# lra.net
KiCad netlist of a schematic drawn in EAGLE
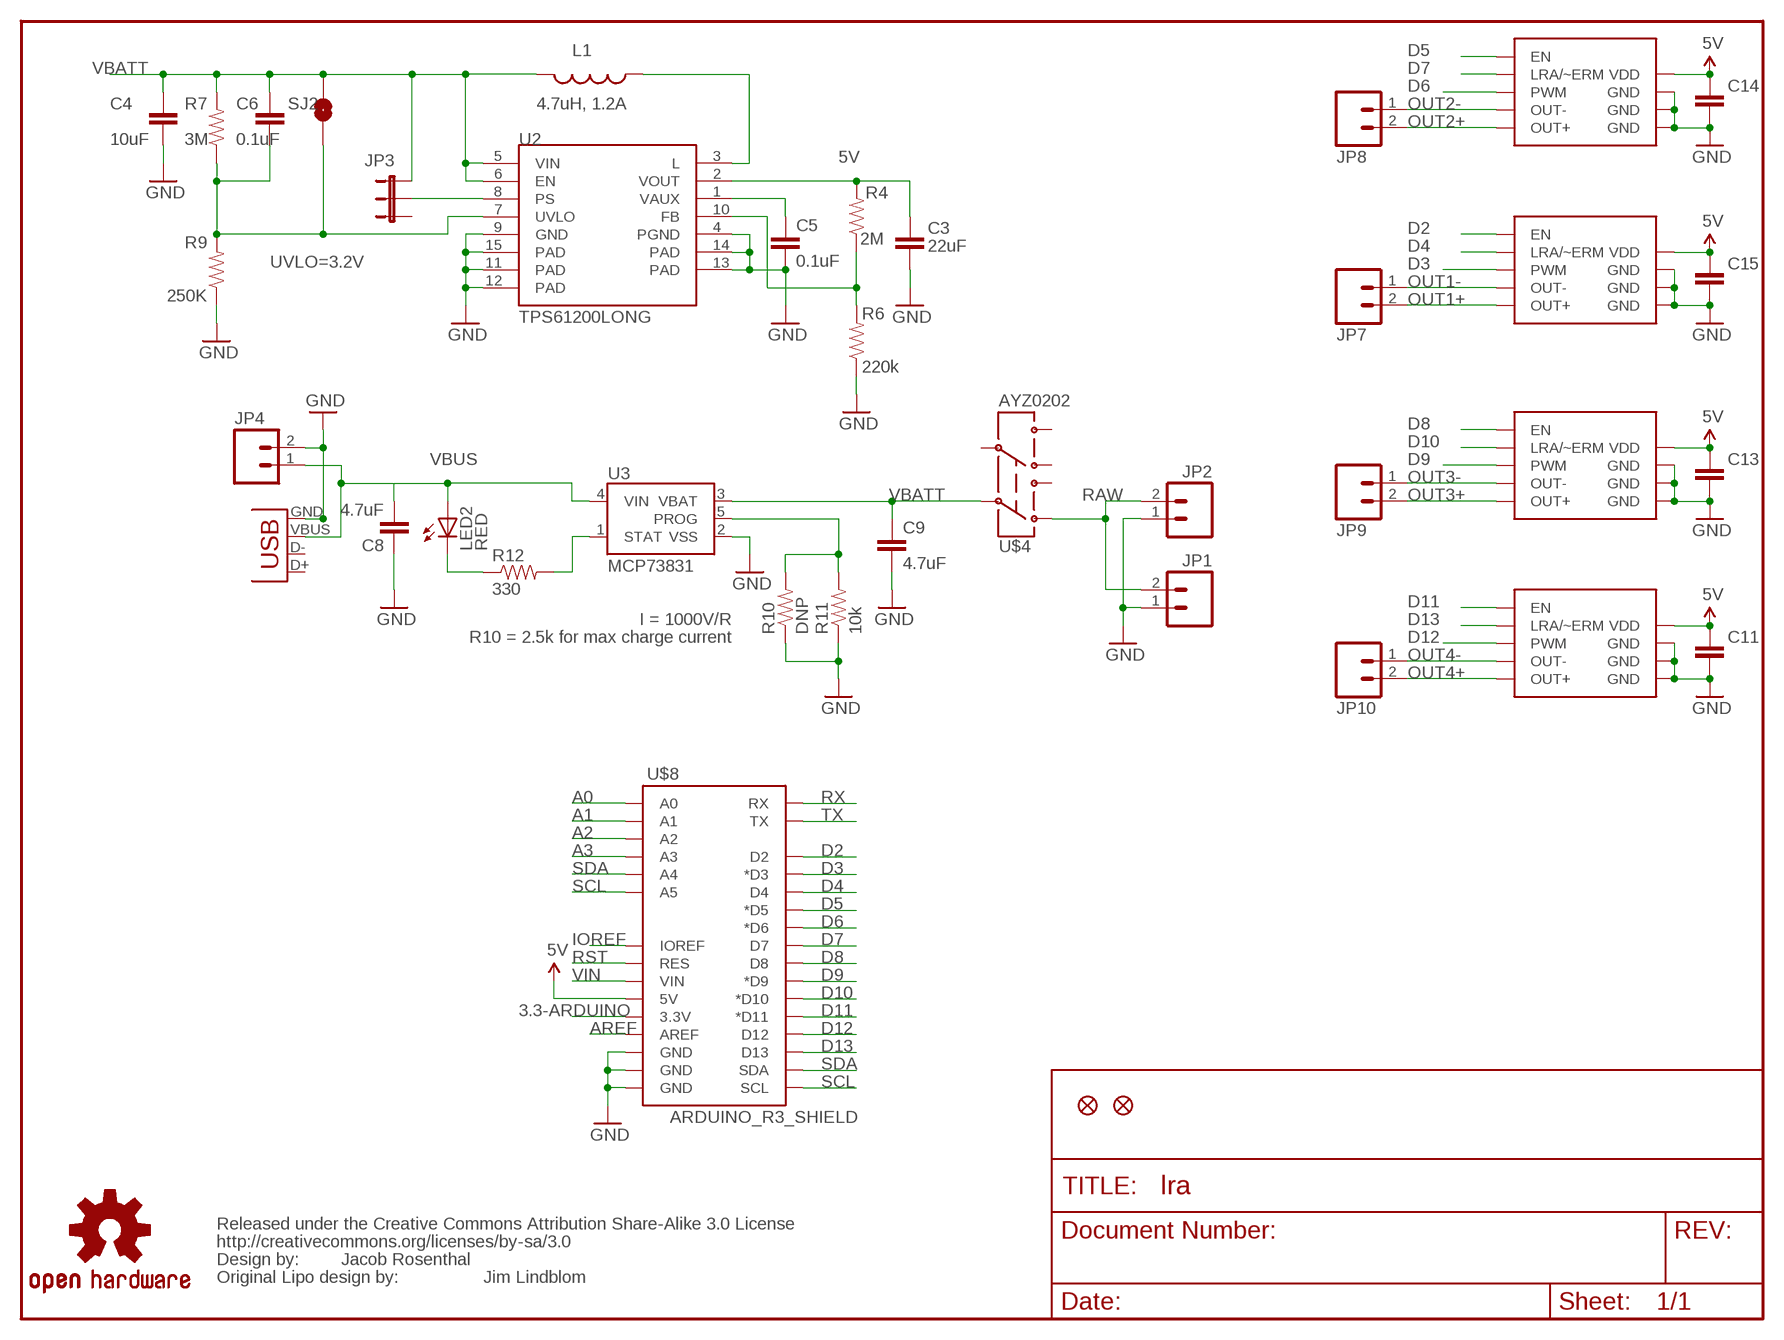
[diagram p0: schematic, sheet 1]

(export (version "E")
  (design (tool "Eeschema 10.0.6"))
  (components
    (comp (ref "$$U$1")
      (value "CREATIVE_COMMONS")
      (footprint "eagle-import:CREATIVE_COMMONS")
      (libsource (lib "eagle-import") (part "CREATIVE_COMMONS"))
    )
    (comp (ref "C3")
      (value "22uF")
      (footprint "eagle-import:0805")
      (libsource (lib "eagle-import") (part "SparkFun_CAP0805"))
    )
    (comp (ref "C4")
      (value "10uF")
      (footprint "eagle-import:0805")
      (libsource (lib "eagle-import") (part "SparkFun_CAP0805"))
    )
    (comp (ref "C5")
      (value "0.1uF")
      (footprint "eagle-import:0805")
      (libsource (lib "eagle-import") (part "SparkFun_CAP0805"))
    )
    (comp (ref "C6")
      (value "0.1uF")
      (footprint "eagle-import:0805")
      (libsource (lib "eagle-import") (part "SparkFun_CAP0805"))
    )
    (comp (ref "C8")
      (value "4.7uF")
      (footprint "eagle-import:0805")
      (libsource (lib "eagle-import") (part "SparkFun_CAP0805"))
    )
    (comp (ref "C9")
      (value "4.7uF")
      (footprint "eagle-import:0805")
      (libsource (lib "eagle-import") (part "SparkFun_CAP0805"))
    )
    (comp (ref "C11")
      (value "CAP0805")
      (footprint "eagle-import:0805")
      (libsource (lib "eagle-import") (part "CAP0805"))
    )
    (comp (ref "C13")
      (value "CAP0805")
      (footprint "eagle-import:0805")
      (libsource (lib "eagle-import") (part "CAP0805"))
    )
    (comp (ref "C14")
      (value "CAP0805")
      (footprint "eagle-import:0805")
      (libsource (lib "eagle-import") (part "CAP0805"))
    )
    (comp (ref "C15")
      (value "CAP0805")
      (footprint "eagle-import:0805")
      (libsource (lib "eagle-import") (part "CAP0805"))
    )
    (comp (ref "JP1")
      (value "M021X02_NO_SILK")
      (footprint "eagle-import:1X02_NO_SILK")
      (libsource (lib "eagle-import") (part "M021X02_NO_SILK"))
    )
    (comp (ref "JP2")
      (value "M02-JST-2MM-SMT")
      (footprint "eagle-import:JST-2-SMD")
      (libsource (lib "eagle-import") (part "M02-JST-2MM-SMT"))
    )
    (comp (ref "JP3")
      (value "JUMPER-32-3")
      (footprint "eagle-import:SJ_3_PASTE2&3")
      (libsource (lib "eagle-import") (part "JUMPER-32-3"))
    )
    (comp (ref "JP4")
      (value "M021X02_NO_SILK")
      (footprint "eagle-import:1X02_NO_SILK")
      (libsource (lib "eagle-import") (part "M021X02_NO_SILK"))
    )
    (comp (ref "JP5")
      (value "FIDUCIAL1X2.5")
      (footprint "eagle-import:FIDUCIAL-1X2.5")
      (libsource (lib "eagle-import") (part "FIDUCIAL1X2.5"))
    )
    (comp (ref "JP6")
      (value "FIDUCIAL1X2.5")
      (footprint "eagle-import:FIDUCIAL-1X2.5")
      (libsource (lib "eagle-import") (part "FIDUCIAL1X2.5"))
    )
    (comp (ref "JP7")
      (value "M02PTH3")
      (footprint "eagle-import:1X02_LONGPADS")
      (libsource (lib "eagle-import") (part "M02PTH3"))
    )
    (comp (ref "JP8")
      (value "M02PTH3")
      (footprint "eagle-import:1X02_LONGPADS")
      (libsource (lib "eagle-import") (part "M02PTH3"))
    )
    (comp (ref "JP9")
      (value "M02PTH3")
      (footprint "eagle-import:1X02_LONGPADS")
      (libsource (lib "eagle-import") (part "M02PTH3"))
    )
    (comp (ref "JP10")
      (value "M02PTH3")
      (footprint "eagle-import:1X02_LONGPADS")
      (libsource (lib "eagle-import") (part "M02PTH3"))
    )
    (comp (ref "L1")
      (value "4.7uH, 1.2A")
      (footprint "eagle-import:CDRH2D09")
      (libsource (lib "eagle-import") (part "INDUCTOR."))
    )
    (comp (ref "LED2")
      (value "RED")
      (footprint "eagle-import:CHIP-LED0805")
      (libsource (lib "eagle-import") (part "LEDCHIP-LED0805"))
    )
    (comp (ref "R4")
      (value "2M")
      (footprint "eagle-import:0805")
      (libsource (lib "eagle-import") (part "RESISTOR0805-RES"))
    )
    (comp (ref "R6")
      (value "220k")
      (footprint "eagle-import:0805")
      (libsource (lib "eagle-import") (part "RESISTOR0805-RES"))
    )
    (comp (ref "R7")
      (value "3M")
      (footprint "eagle-import:0805")
      (libsource (lib "eagle-import") (part "RESISTOR0805-RES"))
    )
    (comp (ref "R9")
      (value "250K")
      (footprint "eagle-import:0805")
      (libsource (lib "eagle-import") (part "RESISTOR0805-RES"))
    )
    (comp (ref "R10")
      (value "DNP")
      (footprint "eagle-import:0805")
      (libsource (lib "eagle-import") (part "RESISTOR0805-RES"))
    )
    (comp (ref "R11")
      (value "10k")
      (footprint "eagle-import:0805")
      (libsource (lib "eagle-import") (part "RESISTOR0805-RES"))
    )
    (comp (ref "R12")
      (value "330")
      (footprint "eagle-import:0805")
      (libsource (lib "eagle-import") (part "RESISTOR0805-RES"))
    )
    (comp (ref "SJ2")
      (value "Power Saving Off")
      (footprint "eagle-import:SJ_2S-NO")
      (libsource (lib "eagle-import") (part "SOLDERJUMPERNO"))
    )
    (comp (ref "U$2")
      (value "DRV260310WFQFN")
      (footprint "eagle-import:10WFQFN")
      (libsource (lib "eagle-import") (part "DRV260310WFQFN"))
    )
    (comp (ref "U$3")
      (value "DRV260310WFQFN")
      (footprint "eagle-import:10WFQFN")
      (libsource (lib "eagle-import") (part "DRV260310WFQFN"))
    )
    (comp (ref "U$4")
      (value "AYZ0202")
      (footprint "eagle-import:AYZ0202")
      (libsource (lib "eagle-import") (part "AYZ0202"))
    )
    (comp (ref "U$6")
      (value "DRV260310WFQFN")
      (footprint "eagle-import:10WFQFN")
      (libsource (lib "eagle-import") (part "DRV260310WFQFN"))
    )
    (comp (ref "U$7")
      (value "DRV2603")
      (footprint "eagle-import:10WFQFN-LONG")
      (libsource (lib "eagle-import") (part "DRV2603"))
    )
    (comp (ref "U$8")
      (value "ARDUINO_R3_SHIELD")
      (footprint "eagle-import:UNO_R3_SHIELD")
      (libsource (lib "eagle-import") (part "ARDUINO_R3_SHIELD"))
    )
    (comp (ref "U$100")
      (value "OSHW-LOGOM")
      (footprint "eagle-import:OSHW-LOGO-M")
      (libsource (lib "eagle-import") (part "OSHW-LOGOM"))
    )
    (comp (ref "U2")
      (value "TPS61200LONG")
      (footprint "eagle-import:QFN-10_PAD_LONG")
      (libsource (lib "eagle-import") (part "TPS61200LONG"))
    )
    (comp (ref "U3")
      (value "MCP73831")
      (footprint "eagle-import:SOT23-5")
      (libsource (lib "eagle-import") (part "MCP73831"))
    )
    (comp (ref "X1")
      (value "USBSMD")
      (footprint "eagle-import:USB-MINIB")
      (libsource (lib "eagle-import") (part "USBSMD"))
    )
  )
  (nets
    (net (code "1") (name "/3.3-ARDUINO") (class "Default")
      (node (ref "U$8") (pin "3.3V") (pinfunction "3.3V_3.3V") (pintype "bidirectional"))
    )
    (net (code "2") (name "/A0") (class "Default")
      (node (ref "U$8") (pin "A0") (pinfunction "A0_A0") (pintype "bidirectional"))
    )
    (net (code "3") (name "/A1") (class "Default")
      (node (ref "U$8") (pin "A1") (pinfunction "A1_A1") (pintype "bidirectional"))
    )
    (net (code "4") (name "/A2") (class "Default")
      (node (ref "U$8") (pin "A2") (pinfunction "A2_A2") (pintype "bidirectional"))
    )
    (net (code "5") (name "/A3") (class "Default")
      (node (ref "U$8") (pin "A3") (pinfunction "A3_A3") (pintype "bidirectional"))
    )
    (net (code "6") (name "/AREF") (class "Default")
      (node (ref "U$8") (pin "AREF") (pinfunction "AREF_AREF") (pintype "bidirectional"))
    )
    (net (code "7") (name "/D2") (class "Default")
      (node (ref "U$3") (pin "P$1") (pinfunction "EN_P$1") (pintype "bidirectional"))
      (node (ref "U$8") (pin "D2") (pinfunction "D2_D2") (pintype "bidirectional"))
    )
    (net (code "8") (name "/D3") (class "Default")
      (node (ref "U$3") (pin "P$2") (pinfunction "PWM_P$2") (pintype "bidirectional"))
      (node (ref "U$8") (pin "D3") (pinfunction "*D3_D3") (pintype "bidirectional"))
    )
    (net (code "9") (name "/D4") (class "Default")
      (node (ref "U$3") (pin "P$3") (pinfunction "LRA/~{ERM}_P$3") (pintype "bidirectional"))
      (node (ref "U$8") (pin "D4") (pinfunction "D4_D4") (pintype "bidirectional"))
    )
    (net (code "10") (name "/D5") (class "Default")
      (node (ref "U$2") (pin "P$1") (pinfunction "EN_P$1") (pintype "bidirectional"))
      (node (ref "U$8") (pin "D5") (pinfunction "*D5_D5") (pintype "bidirectional"))
    )
    (net (code "11") (name "/D6") (class "Default")
      (node (ref "U$2") (pin "P$2") (pinfunction "PWM_P$2") (pintype "bidirectional"))
      (node (ref "U$8") (pin "D6") (pinfunction "*D6_D6") (pintype "bidirectional"))
    )
    (net (code "12") (name "/D7") (class "Default")
      (node (ref "U$2") (pin "P$3") (pinfunction "LRA/~{ERM}_P$3") (pintype "bidirectional"))
      (node (ref "U$8") (pin "D7") (pinfunction "D7_D7") (pintype "bidirectional"))
    )
    (net (code "13") (name "/D8") (class "Default")
      (node (ref "U$6") (pin "P$1") (pinfunction "EN_P$1") (pintype "bidirectional"))
      (node (ref "U$8") (pin "D8") (pinfunction "D8_D8") (pintype "bidirectional"))
    )
    (net (code "14") (name "/D9") (class "Default")
      (node (ref "U$6") (pin "P$2") (pinfunction "PWM_P$2") (pintype "bidirectional"))
      (node (ref "U$8") (pin "D9") (pinfunction "*D9_D9") (pintype "bidirectional"))
    )
    (net (code "15") (name "/D10") (class "Default")
      (node (ref "U$6") (pin "P$3") (pinfunction "LRA/~{ERM}_P$3") (pintype "bidirectional"))
      (node (ref "U$8") (pin "D10") (pinfunction "*D10_D10") (pintype "bidirectional"))
    )
    (net (code "16") (name "/D11") (class "Default")
      (node (ref "U$7") (pin "P$1") (pinfunction "EN_P$1") (pintype "bidirectional"))
      (node (ref "U$8") (pin "D11") (pinfunction "*D11_D11") (pintype "bidirectional"))
    )
    (net (code "17") (name "/D12") (class "Default")
      (node (ref "U$7") (pin "P$2") (pinfunction "PWM_P$2") (pintype "bidirectional"))
      (node (ref "U$8") (pin "D12") (pinfunction "D12_D12") (pintype "bidirectional"))
    )
    (net (code "18") (name "/D13") (class "Default")
      (node (ref "U$7") (pin "P$3") (pinfunction "LRA/~{ERM}_P$3") (pintype "bidirectional"))
      (node (ref "U$8") (pin "D13") (pinfunction "D13_D13") (pintype "bidirectional"))
    )
    (net (code "19") (name "/IOREF") (class "Default")
      (node (ref "U$8") (pin "IOREF") (pinfunction "IOREF_IOREF") (pintype "bidirectional"))
    )
    (net (code "20") (name "/OUT1+") (class "Default")
      (node (ref "JP7") (pin "2") (pinfunction "2_2") (pintype "passive"))
      (node (ref "U$3") (pin "P$9") (pinfunction "OUT+_P$9") (pintype "bidirectional"))
    )
    (net (code "21") (name "/OUT1-") (class "Default")
      (node (ref "JP7") (pin "1") (pinfunction "1_1") (pintype "passive"))
      (node (ref "U$3") (pin "P$6") (pinfunction "OUT-_P$6") (pintype "bidirectional"))
    )
    (net (code "22") (name "/OUT2+") (class "Default")
      (node (ref "JP8") (pin "2") (pinfunction "2_2") (pintype "passive"))
      (node (ref "U$2") (pin "P$9") (pinfunction "OUT+_P$9") (pintype "bidirectional"))
    )
    (net (code "23") (name "/OUT2-") (class "Default")
      (node (ref "JP8") (pin "1") (pinfunction "1_1") (pintype "passive"))
      (node (ref "U$2") (pin "P$6") (pinfunction "OUT-_P$6") (pintype "bidirectional"))
    )
    (net (code "24") (name "/OUT3+") (class "Default")
      (node (ref "JP9") (pin "2") (pinfunction "2_2") (pintype "passive"))
      (node (ref "U$6") (pin "P$9") (pinfunction "OUT+_P$9") (pintype "bidirectional"))
    )
    (net (code "25") (name "/OUT3-") (class "Default")
      (node (ref "JP9") (pin "1") (pinfunction "1_1") (pintype "passive"))
      (node (ref "U$6") (pin "P$6") (pinfunction "OUT-_P$6") (pintype "bidirectional"))
    )
    (net (code "26") (name "/OUT4+") (class "Default")
      (node (ref "JP10") (pin "2") (pinfunction "2_2") (pintype "passive"))
      (node (ref "U$7") (pin "P$9") (pinfunction "OUT+_P$9") (pintype "bidirectional"))
    )
    (net (code "27") (name "/OUT4-") (class "Default")
      (node (ref "JP10") (pin "1") (pinfunction "1_1") (pintype "passive"))
      (node (ref "U$7") (pin "P$6") (pinfunction "OUT-_P$6") (pintype "bidirectional"))
    )
    (net (code "28") (name "/RAW") (class "Default")
      (node (ref "JP1") (pin "2") (pinfunction "2_2") (pintype "passive"))
      (node (ref "JP2") (pin "2") (pinfunction "2_2") (pintype "passive"))
      (node (ref "U$4") (pin "3") (pinfunction "1_3") (pintype "bidirectional"))
    )
    (net (code "29") (name "/RST") (class "Default")
      (node (ref "U$8") (pin "RES") (pinfunction "RES_RES") (pintype "bidirectional"))
    )
    (net (code "30") (name "/RX") (class "Default")
      (node (ref "U$8") (pin "RX") (pinfunction "RX_RX") (pintype "bidirectional"))
    )
    (net (code "31") (name "/SCL") (class "Default")
      (node (ref "U$8") (pin "A5") (pinfunction "A5_A5") (pintype "bidirectional"))
      (node (ref "U$8") (pin "SCL") (pinfunction "SCL_SCL") (pintype "bidirectional"))
    )
    (net (code "32") (name "/SDA") (class "Default")
      (node (ref "U$8") (pin "A4") (pinfunction "A4_A4") (pintype "bidirectional"))
      (node (ref "U$8") (pin "SDA") (pinfunction "SDA_SDA") (pintype "bidirectional"))
    )
    (net (code "33") (name "/TX") (class "Default")
      (node (ref "U$8") (pin "TX") (pinfunction "TX_TX") (pintype "bidirectional"))
    )
    (net (code "34") (name "/VBATT") (class "Default")
      (node (ref "C4") (pin "1") (pinfunction "1_1") (pintype "passive"))
      (node (ref "C6") (pin "1") (pinfunction "1_1") (pintype "passive"))
      (node (ref "C9") (pin "1") (pinfunction "1_1") (pintype "passive"))
      (node (ref "JP3") (pin "3") (pinfunction "3_3") (pintype "passive"))
      (node (ref "L1") (pin "P$2") (pinfunction "2_P$2") (pintype "passive"))
      (node (ref "R7") (pin "2") (pinfunction "2_2") (pintype "passive"))
      (node (ref "SJ2") (pin "2") (pinfunction "2_2") (pintype "passive"))
      (node (ref "U$4") (pin "2") (pinfunction "2_2") (pintype "bidirectional"))
      (node (ref "U2") (pin "5") (pinfunction "VIN_5") (pintype "power_in"))
      (node (ref "U2") (pin "6") (pinfunction "EN_6") (pintype "input"))
      (node (ref "U3") (pin "3") (pinfunction "VBAT_3") (pintype "power_in"))
    )
    (net (code "35") (name "/VBUS") (class "Default")
      (node (ref "C8") (pin "2") (pinfunction "2_2") (pintype "passive"))
      (node (ref "JP4") (pin "1") (pinfunction "1_1") (pintype "passive"))
      (node (ref "LED2") (pin "A") (pinfunction "A_A") (pintype "passive"))
      (node (ref "U3") (pin "4") (pinfunction "VIN_4") (pintype "power_in"))
      (node (ref "X1") (pin "VBUS") (pinfunction "VBUS_VBUS") (pintype "bidirectional"))
    )
    (net (code "36") (name "/VIN") (class "Default")
      (node (ref "U$8") (pin "VIN") (pinfunction "VIN_VIN") (pintype "bidirectional"))
    )
    (net (code "37") (name "5V") (class "Default")
      (node (ref "C11") (pin "1") (pinfunction "1_1") (pintype "passive"))
      (node (ref "C13") (pin "1") (pinfunction "1_1") (pintype "passive"))
      (node (ref "C14") (pin "1") (pinfunction "1_1") (pintype "passive"))
      (node (ref "C15") (pin "1") (pinfunction "1_1") (pintype "passive"))
      (node (ref "C3") (pin "1") (pinfunction "1_1") (pintype "passive"))
      (node (ref "R4") (pin "2") (pinfunction "2_2") (pintype "passive"))
      (node (ref "U$2") (pin "P$7") (pinfunction "VDD_P$7") (pintype "bidirectional"))
      (node (ref "U$3") (pin "P$7") (pinfunction "VDD_P$7") (pintype "bidirectional"))
      (node (ref "U$6") (pin "P$7") (pinfunction "VDD_P$7") (pintype "bidirectional"))
      (node (ref "U$7") (pin "P$7") (pinfunction "VDD_P$7") (pintype "bidirectional"))
      (node (ref "U$8") (pin "5V") (pinfunction "5V_5V") (pintype "bidirectional"))
      (node (ref "U2") (pin "2") (pinfunction "VOUT_2") (pintype "passive"))
    )
    (net (code "38") (name "GND") (class "Default")
      (node (ref "C11") (pin "2") (pinfunction "2_2") (pintype "passive"))
      (node (ref "C13") (pin "2") (pinfunction "2_2") (pintype "passive"))
      (node (ref "C14") (pin "2") (pinfunction "2_2") (pintype "passive"))
      (node (ref "C15") (pin "2") (pinfunction "2_2") (pintype "passive"))
      (node (ref "C3") (pin "2") (pinfunction "2_2") (pintype "passive"))
      (node (ref "C4") (pin "2") (pinfunction "2_2") (pintype "passive"))
      (node (ref "C5") (pin "2") (pinfunction "2_2") (pintype "passive"))
      (node (ref "C8") (pin "1") (pinfunction "1_1") (pintype "passive"))
      (node (ref "C9") (pin "2") (pinfunction "2_2") (pintype "passive"))
      (node (ref "JP1") (pin "1") (pinfunction "1_1") (pintype "passive"))
      (node (ref "JP2") (pin "1") (pinfunction "1_1") (pintype "passive"))
      (node (ref "JP4") (pin "2") (pinfunction "2_2") (pintype "passive"))
      (node (ref "R10") (pin "1") (pinfunction "1_1") (pintype "passive"))
      (node (ref "R11") (pin "1") (pinfunction "1_1") (pintype "passive"))
      (node (ref "R6") (pin "1") (pinfunction "1_1") (pintype "passive"))
      (node (ref "R9") (pin "1") (pinfunction "1_1") (pintype "passive"))
      (node (ref "U$2") (pin "GND@1") (pinfunction "GND_GND@1") (pintype "bidirectional"))
      (node (ref "U$2") (pin "GND@2") (pinfunction "GND_GND@2") (pintype "bidirectional"))
      (node (ref "U$2") (pin "GND@3") (pinfunction "GND_GND@3") (pintype "bidirectional"))
      (node (ref "U$3") (pin "GND@1") (pinfunction "GND_GND@1") (pintype "bidirectional"))
      (node (ref "U$3") (pin "GND@2") (pinfunction "GND_GND@2") (pintype "bidirectional"))
      (node (ref "U$3") (pin "GND@3") (pinfunction "GND_GND@3") (pintype "bidirectional"))
      (node (ref "U$6") (pin "GND@1") (pinfunction "GND_GND@1") (pintype "bidirectional"))
      (node (ref "U$6") (pin "GND@2") (pinfunction "GND_GND@2") (pintype "bidirectional"))
      (node (ref "U$6") (pin "GND@3") (pinfunction "GND_GND@3") (pintype "bidirectional"))
      (node (ref "U$7") (pin "GND@1") (pinfunction "GND_GND@1") (pintype "bidirectional"))
      (node (ref "U$7") (pin "GND@2") (pinfunction "GND_GND@2") (pintype "bidirectional"))
      (node (ref "U$7") (pin "GND@3") (pinfunction "GND_GND@3") (pintype "bidirectional"))
      (node (ref "U$8") (pin "GND@0") (pinfunction "GND_GND@0") (pintype "bidirectional"))
      (node (ref "U$8") (pin "GND@1") (pinfunction "GND_GND@1") (pintype "bidirectional"))
      (node (ref "U$8") (pin "GND@2") (pinfunction "GND_GND@2") (pintype "bidirectional"))
      (node (ref "U2") (pin "11") (pinfunction "PAD_11") (pintype "power_in"))
      (node (ref "U2") (pin "12") (pinfunction "PAD_12") (pintype "power_in"))
      (node (ref "U2") (pin "13") (pinfunction "PAD_13") (pintype "power_in"))
      (node (ref "U2") (pin "14") (pinfunction "PAD_14") (pintype "power_in"))
      (node (ref "U2") (pin "15") (pinfunction "PAD_15") (pintype "power_in"))
      (node (ref "U2") (pin "4") (pinfunction "PGND_4") (pintype "power_in"))
      (node (ref "U2") (pin "9") (pinfunction "GND_9") (pintype "power_in"))
      (node (ref "U3") (pin "2") (pinfunction "VSS_2") (pintype "power_in"))
      (node (ref "X1") (pin "GND") (pinfunction "GND_GND") (pintype "bidirectional"))
    )
    (net (code "39") (name "Net-(L1-1)") (class "Default")
      (node (ref "L1") (pin "P$1") (pinfunction "1_P$1") (pintype "passive"))
      (node (ref "U2") (pin "3") (pinfunction "L_3") (pintype "passive"))
    )
    (net (code "40") (name "Net-(LED2-PadC)") (class "Default")
      (node (ref "LED2") (pin "C") (pinfunction "C_C") (pintype "passive"))
      (node (ref "R12") (pin "1") (pinfunction "1_1") (pintype "passive"))
    )
    (net (code "41") (name "Net-(U2-FB)") (class "Default")
      (node (ref "R4") (pin "1") (pinfunction "1_1") (pintype "passive"))
      (node (ref "R6") (pin "2") (pinfunction "2_2") (pintype "passive"))
      (node (ref "U2") (pin "10") (pinfunction "FB_10") (pintype "passive"))
    )
    (net (code "42") (name "Net-(U2-PS)") (class "Default")
      (node (ref "JP3") (pin "2") (pinfunction "2_2") (pintype "passive"))
      (node (ref "U2") (pin "8") (pinfunction "PS_8") (pintype "input"))
    )
    (net (code "43") (name "Net-(U2-UVLO)") (class "Default")
      (node (ref "C6") (pin "2") (pinfunction "2_2") (pintype "passive"))
      (node (ref "R7") (pin "1") (pinfunction "1_1") (pintype "passive"))
      (node (ref "R9") (pin "2") (pinfunction "2_2") (pintype "passive"))
      (node (ref "SJ2") (pin "1") (pinfunction "1_1") (pintype "passive"))
      (node (ref "U2") (pin "7") (pinfunction "UVLO_7") (pintype "passive"))
    )
    (net (code "44") (name "Net-(U2-VAUX)") (class "Default")
      (node (ref "C5") (pin "1") (pinfunction "1_1") (pintype "passive"))
      (node (ref "U2") (pin "1") (pinfunction "VAUX_1") (pintype "passive"))
    )
    (net (code "45") (name "Net-(U3-PROG)") (class "Default")
      (node (ref "R10") (pin "2") (pinfunction "2_2") (pintype "passive"))
      (node (ref "R11") (pin "2") (pinfunction "2_2") (pintype "passive"))
      (node (ref "U3") (pin "5") (pinfunction "PROG_5") (pintype "input"))
    )
    (net (code "46") (name "Net-(U3-STAT)") (class "Default")
      (node (ref "R12") (pin "2") (pinfunction "2_2") (pintype "passive"))
      (node (ref "U3") (pin "1") (pinfunction "STAT_1") (pintype "output"))
    )
    (net (code "47") (name "unconnected-(JP3-Pad1)") (class "Default")
      (node (ref "JP3") (pin "1") (pinfunction "1_1") (pintype "passive"))
    )
    (net (code "48") (name "unconnected-(U$4-3-Pad1)") (class "Default")
      (node (ref "U$4") (pin "1") (pinfunction "3_1") (pintype "bidirectional"))
    )
    (net (code "49") (name "unconnected-(U$4-4-Pad6)") (class "Default")
      (node (ref "U$4") (pin "6") (pinfunction "4_6") (pintype "bidirectional"))
    )
    (net (code "50") (name "unconnected-(U$4-6-Pad4)") (class "Default")
      (node (ref "U$4") (pin "4") (pinfunction "6_4") (pintype "bidirectional"))
    )
    (net (code "51") (name "unconnected-(U$4-Pad5)") (class "Default")
      (node (ref "U$4") (pin "5") (pinfunction "5_5") (pintype "bidirectional"))
    )
    (net (code "52") (name "unconnected-(X1-PadD+)") (class "Default")
      (node (ref "X1") (pin "D+") (pinfunction "D+_D+") (pintype "bidirectional"))
    )
    (net (code "53") (name "unconnected-(X1-PadD-)") (class "Default")
      (node (ref "X1") (pin "D-") (pinfunction "D-_D-") (pintype "bidirectional"))
    )
  )
)
